# button-led-matrix-4x4.net
KiCad netlist of a schematic drawn in EAGLE
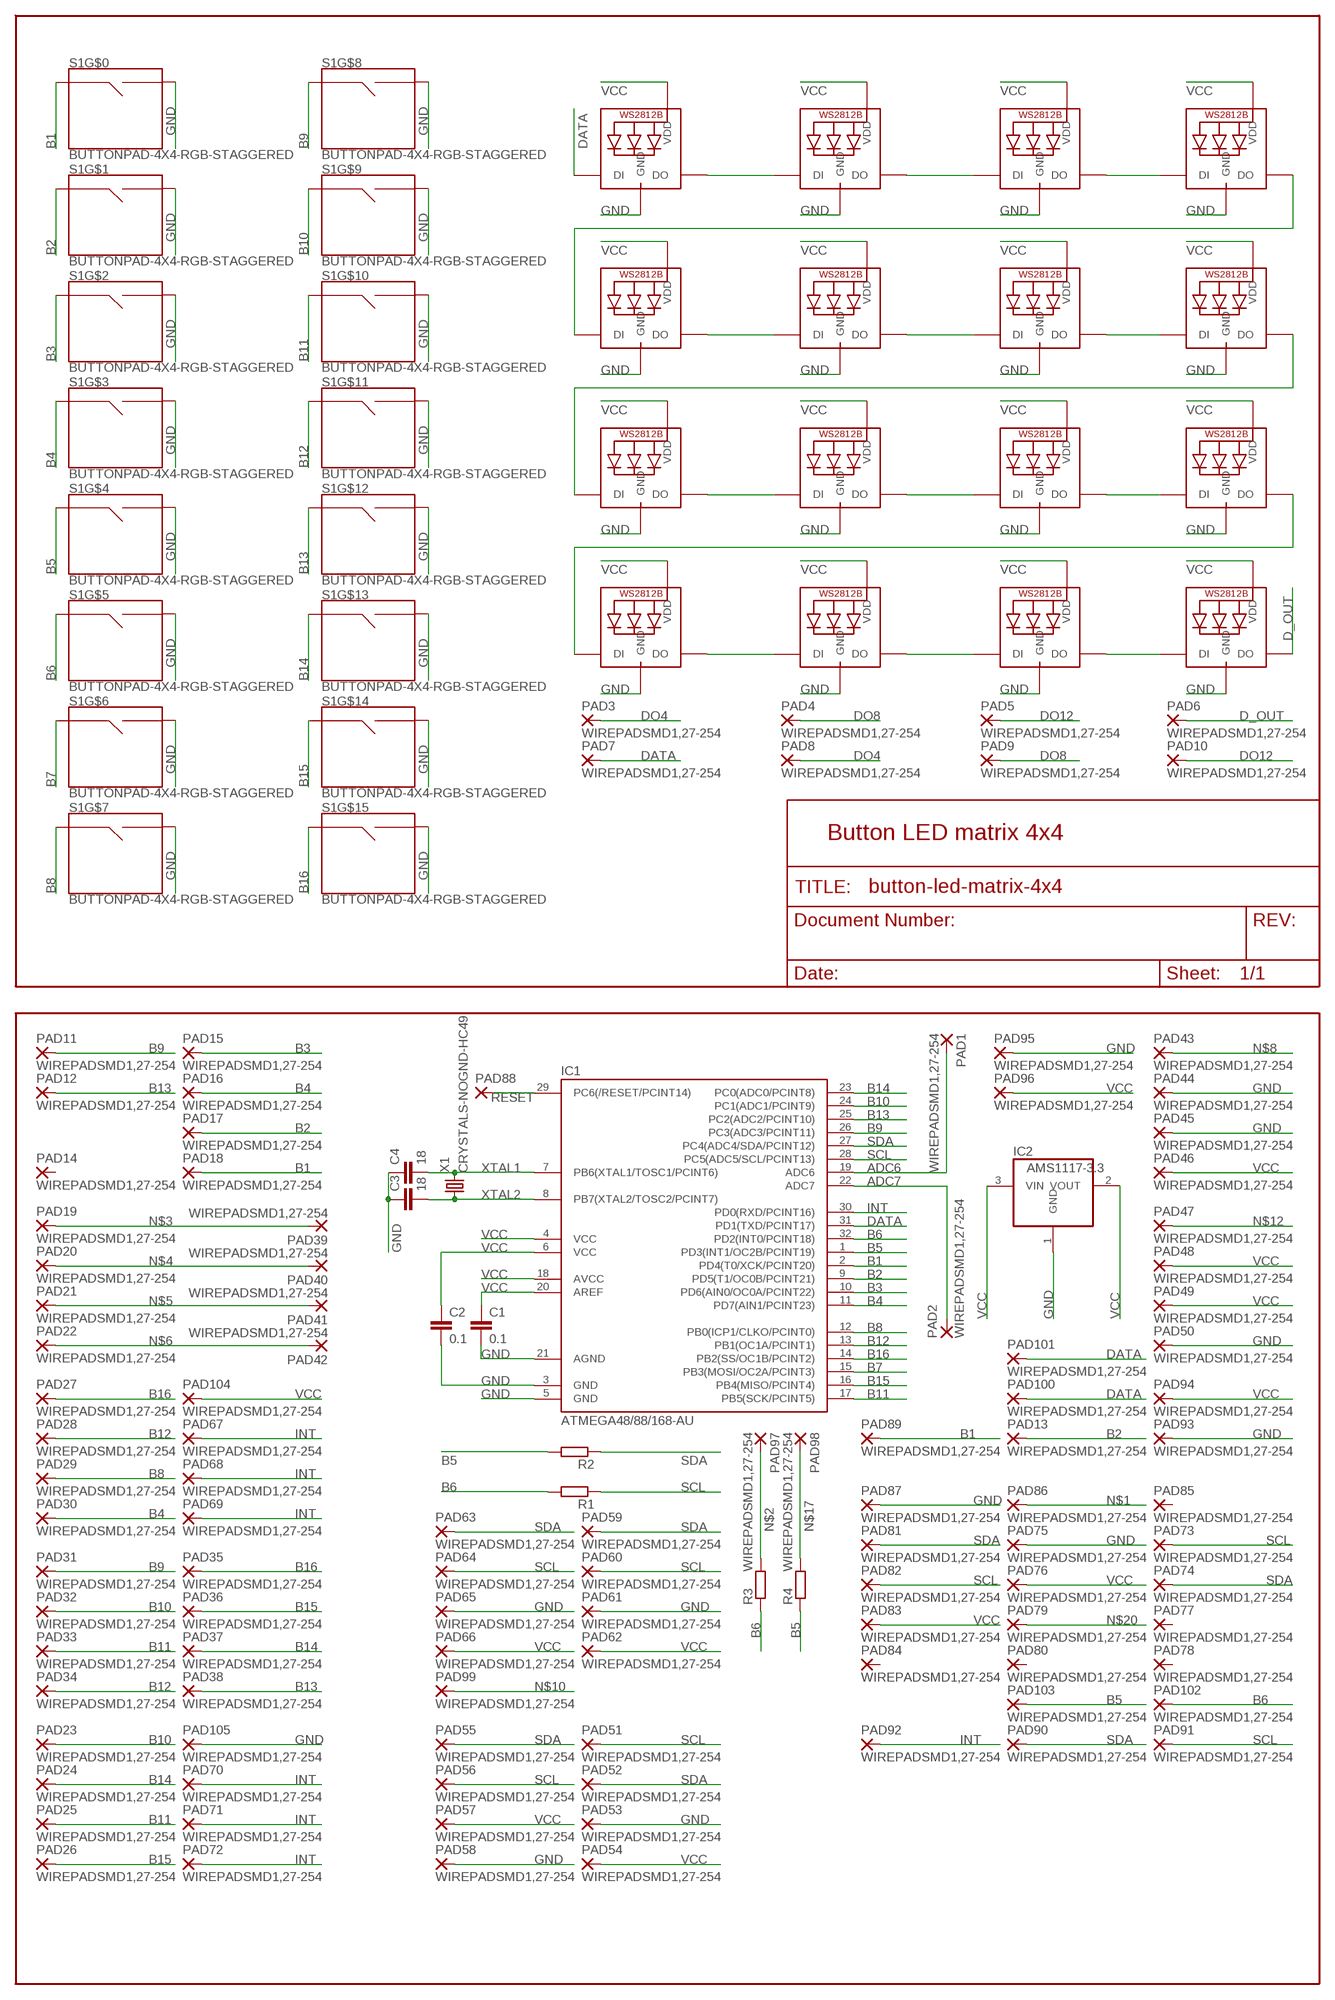
[diagram p0: schematic, sheet 1]

(export (version "E")
  (design (tool "Eeschema 10.0.6"))
  (components
    (comp (ref "C1")
      (value "0.1")
      (footprint "eagle-import:C0805")
      (libsource (lib "eagle-import") (part "C-EUC0805"))
    )
    (comp (ref "C2")
      (value "0.1")
      (footprint "eagle-import:C0805")
      (libsource (lib "eagle-import") (part "C-EUC0805"))
    )
    (comp (ref "C3")
      (value "18")
      (footprint "eagle-import:C0805")
      (libsource (lib "eagle-import") (part "C-EUC0805"))
    )
    (comp (ref "C4")
      (value "18")
      (footprint "eagle-import:C0805")
      (libsource (lib "eagle-import") (part "C-EUC0805"))
    )
    (comp (ref "IC1")
      (value "ATMEGA48/88/168-AU")
      (footprint "eagle-import:TQFP32-08")
      (libsource (lib "eagle-import") (part "ATMEGA48/88/168-AU"))
    )
    (comp (ref "IC2")
      (value "AMS1117-3.3")
      (footprint "eagle-import:SOT223")
      (fields (field (name "MPN") "REG1117"))
      (libsource (lib "eagle-import") (part "REG1117"))
    )
    (comp (ref "LED1")
      (value "WS2812B_5050N")
      (footprint "eagle-import:WS2812B-NARROW")
      (libsource (lib "eagle-import") (part "WS2812B_5050N"))
    )
    (comp (ref "LED2")
      (value "WS2812B_5050N")
      (footprint "eagle-import:WS2812B-NARROW")
      (libsource (lib "eagle-import") (part "WS2812B_5050N"))
    )
    (comp (ref "LED3")
      (value "WS2812B_5050N")
      (footprint "eagle-import:WS2812B-NARROW")
      (libsource (lib "eagle-import") (part "WS2812B_5050N"))
    )
    (comp (ref "LED4")
      (value "WS2812B_5050N")
      (footprint "eagle-import:WS2812B-NARROW")
      (libsource (lib "eagle-import") (part "WS2812B_5050N"))
    )
    (comp (ref "LED5")
      (value "WS2812B_5050N")
      (footprint "eagle-import:WS2812B-NARROW")
      (libsource (lib "eagle-import") (part "WS2812B_5050N"))
    )
    (comp (ref "LED6")
      (value "WS2812B_5050N")
      (footprint "eagle-import:WS2812B-NARROW")
      (libsource (lib "eagle-import") (part "WS2812B_5050N"))
    )
    (comp (ref "LED7")
      (value "WS2812B_5050N")
      (footprint "eagle-import:WS2812B-NARROW")
      (libsource (lib "eagle-import") (part "WS2812B_5050N"))
    )
    (comp (ref "LED8")
      (value "WS2812B_5050N")
      (footprint "eagle-import:WS2812B-NARROW")
      (libsource (lib "eagle-import") (part "WS2812B_5050N"))
    )
    (comp (ref "LED9")
      (value "WS2812B_5050N")
      (footprint "eagle-import:WS2812B-NARROW")
      (libsource (lib "eagle-import") (part "WS2812B_5050N"))
    )
    (comp (ref "LED10")
      (value "WS2812B_5050N")
      (footprint "eagle-import:WS2812B-NARROW")
      (libsource (lib "eagle-import") (part "WS2812B_5050N"))
    )
    (comp (ref "LED11")
      (value "WS2812B_5050N")
      (footprint "eagle-import:WS2812B-NARROW")
      (libsource (lib "eagle-import") (part "WS2812B_5050N"))
    )
    (comp (ref "LED12")
      (value "WS2812B_5050N")
      (footprint "eagle-import:WS2812B-NARROW")
      (libsource (lib "eagle-import") (part "WS2812B_5050N"))
    )
    (comp (ref "LED13")
      (value "WS2812B_5050N")
      (footprint "eagle-import:WS2812B-NARROW")
      (libsource (lib "eagle-import") (part "WS2812B_5050N"))
    )
    (comp (ref "LED14")
      (value "WS2812B_5050N")
      (footprint "eagle-import:WS2812B-NARROW")
      (libsource (lib "eagle-import") (part "WS2812B_5050N"))
    )
    (comp (ref "LED15")
      (value "WS2812B_5050N")
      (footprint "eagle-import:WS2812B-NARROW")
      (libsource (lib "eagle-import") (part "WS2812B_5050N"))
    )
    (comp (ref "LED16")
      (value "WS2812B_5050N")
      (footprint "eagle-import:WS2812B-NARROW")
      (libsource (lib "eagle-import") (part "WS2812B_5050N"))
    )
    (comp (ref "PAD1")
      (value "WIREPADSMD1,27-254")
      (footprint "eagle-import:SMD1,27-2,54")
      (libsource (lib "eagle-import") (part "WIREPADSMD1,27-254"))
    )
    (comp (ref "PAD2")
      (value "WIREPADSMD1,27-254")
      (footprint "eagle-import:SMD1,27-2,54")
      (libsource (lib "eagle-import") (part "WIREPADSMD1,27-254"))
    )
    (comp (ref "PAD3")
      (value "WIREPADSMD1,27-254")
      (footprint "eagle-import:SMD1,27-2,54")
      (libsource (lib "eagle-import") (part "WIREPADSMD1,27-254"))
    )
    (comp (ref "PAD4")
      (value "WIREPADSMD1,27-254")
      (footprint "eagle-import:SMD1,27-2,54")
      (libsource (lib "eagle-import") (part "WIREPADSMD1,27-254"))
    )
    (comp (ref "PAD5")
      (value "WIREPADSMD1,27-254")
      (footprint "eagle-import:SMD1,27-2,54")
      (libsource (lib "eagle-import") (part "WIREPADSMD1,27-254"))
    )
    (comp (ref "PAD6")
      (value "WIREPADSMD1,27-254")
      (footprint "eagle-import:SMD1,27-2,54")
      (libsource (lib "eagle-import") (part "WIREPADSMD1,27-254"))
    )
    (comp (ref "PAD7")
      (value "WIREPADSMD1,27-254")
      (footprint "eagle-import:SMD1,27-2,54")
      (libsource (lib "eagle-import") (part "WIREPADSMD1,27-254"))
    )
    (comp (ref "PAD8")
      (value "WIREPADSMD1,27-254")
      (footprint "eagle-import:SMD1,27-2,54")
      (libsource (lib "eagle-import") (part "WIREPADSMD1,27-254"))
    )
    (comp (ref "PAD9")
      (value "WIREPADSMD1,27-254")
      (footprint "eagle-import:SMD1,27-2,54")
      (libsource (lib "eagle-import") (part "WIREPADSMD1,27-254"))
    )
    (comp (ref "PAD10")
      (value "WIREPADSMD1,27-254")
      (footprint "eagle-import:SMD1,27-2,54")
      (libsource (lib "eagle-import") (part "WIREPADSMD1,27-254"))
    )
    (comp (ref "PAD11")
      (value "WIREPADSMD1,27-254")
      (footprint "eagle-import:SMD1,27-2,54")
      (libsource (lib "eagle-import") (part "WIREPADSMD1,27-254"))
    )
    (comp (ref "PAD12")
      (value "WIREPADSMD1,27-254")
      (footprint "eagle-import:SMD1,27-2,54")
      (libsource (lib "eagle-import") (part "WIREPADSMD1,27-254"))
    )
    (comp (ref "PAD13")
      (value "WIREPADSMD1,27-254")
      (footprint "eagle-import:SMD1,27-2,54")
      (libsource (lib "eagle-import") (part "WIREPADSMD1,27-254"))
    )
    (comp (ref "PAD14")
      (value "WIREPADSMD1,27-254")
      (footprint "eagle-import:SMD1,27-2,54")
      (libsource (lib "eagle-import") (part "WIREPADSMD1,27-254"))
    )
    (comp (ref "PAD15")
      (value "WIREPADSMD1,27-254")
      (footprint "eagle-import:SMD1,27-2,54")
      (libsource (lib "eagle-import") (part "WIREPADSMD1,27-254"))
    )
    (comp (ref "PAD16")
      (value "WIREPADSMD1,27-254")
      (footprint "eagle-import:SMD1,27-2,54")
      (libsource (lib "eagle-import") (part "WIREPADSMD1,27-254"))
    )
    (comp (ref "PAD17")
      (value "WIREPADSMD1,27-254")
      (footprint "eagle-import:SMD1,27-2,54")
      (libsource (lib "eagle-import") (part "WIREPADSMD1,27-254"))
    )
    (comp (ref "PAD18")
      (value "WIREPADSMD1,27-254")
      (footprint "eagle-import:SMD1,27-2,54")
      (libsource (lib "eagle-import") (part "WIREPADSMD1,27-254"))
    )
    (comp (ref "PAD19")
      (value "WIREPADSMD1,27-254")
      (footprint "eagle-import:SMD1,27-2,54")
      (libsource (lib "eagle-import") (part "WIREPADSMD1,27-254"))
    )
    (comp (ref "PAD20")
      (value "WIREPADSMD1,27-254")
      (footprint "eagle-import:SMD1,27-2,54")
      (libsource (lib "eagle-import") (part "WIREPADSMD1,27-254"))
    )
    (comp (ref "PAD21")
      (value "WIREPADSMD1,27-254")
      (footprint "eagle-import:SMD1,27-2,54")
      (libsource (lib "eagle-import") (part "WIREPADSMD1,27-254"))
    )
    (comp (ref "PAD22")
      (value "WIREPADSMD1,27-254")
      (footprint "eagle-import:SMD1,27-2,54")
      (libsource (lib "eagle-import") (part "WIREPADSMD1,27-254"))
    )
    (comp (ref "PAD23")
      (value "WIREPADSMD1,27-254")
      (footprint "eagle-import:SMD1,27-2,54")
      (libsource (lib "eagle-import") (part "WIREPADSMD1,27-254"))
    )
    (comp (ref "PAD24")
      (value "WIREPADSMD1,27-254")
      (footprint "eagle-import:SMD1,27-2,54")
      (libsource (lib "eagle-import") (part "WIREPADSMD1,27-254"))
    )
    (comp (ref "PAD25")
      (value "WIREPADSMD1,27-254")
      (footprint "eagle-import:SMD1,27-2,54")
      (libsource (lib "eagle-import") (part "WIREPADSMD1,27-254"))
    )
    (comp (ref "PAD26")
      (value "WIREPADSMD1,27-254")
      (footprint "eagle-import:SMD1,27-2,54")
      (libsource (lib "eagle-import") (part "WIREPADSMD1,27-254"))
    )
    (comp (ref "PAD27")
      (value "WIREPADSMD1,27-254")
      (footprint "eagle-import:SMD1,27-2,54")
      (libsource (lib "eagle-import") (part "WIREPADSMD1,27-254"))
    )
    (comp (ref "PAD28")
      (value "WIREPADSMD1,27-254")
      (footprint "eagle-import:SMD1,27-2,54")
      (libsource (lib "eagle-import") (part "WIREPADSMD1,27-254"))
    )
    (comp (ref "PAD29")
      (value "WIREPADSMD1,27-254")
      (footprint "eagle-import:SMD1,27-2,54")
      (libsource (lib "eagle-import") (part "WIREPADSMD1,27-254"))
    )
    (comp (ref "PAD30")
      (value "WIREPADSMD1,27-254")
      (footprint "eagle-import:SMD1,27-2,54")
      (libsource (lib "eagle-import") (part "WIREPADSMD1,27-254"))
    )
    (comp (ref "PAD31")
      (value "WIREPADSMD1,27-254")
      (footprint "eagle-import:SMD1,27-2,54")
      (libsource (lib "eagle-import") (part "WIREPADSMD1,27-254"))
    )
    (comp (ref "PAD32")
      (value "WIREPADSMD1,27-254")
      (footprint "eagle-import:SMD1,27-2,54")
      (libsource (lib "eagle-import") (part "WIREPADSMD1,27-254"))
    )
    (comp (ref "PAD33")
      (value "WIREPADSMD1,27-254")
      (footprint "eagle-import:SMD1,27-2,54")
      (libsource (lib "eagle-import") (part "WIREPADSMD1,27-254"))
    )
    (comp (ref "PAD34")
      (value "WIREPADSMD1,27-254")
      (footprint "eagle-import:SMD1,27-2,54")
      (libsource (lib "eagle-import") (part "WIREPADSMD1,27-254"))
    )
    (comp (ref "PAD35")
      (value "WIREPADSMD1,27-254")
      (footprint "eagle-import:SMD1,27-2,54")
      (libsource (lib "eagle-import") (part "WIREPADSMD1,27-254"))
    )
    (comp (ref "PAD36")
      (value "WIREPADSMD1,27-254")
      (footprint "eagle-import:SMD1,27-2,54")
      (libsource (lib "eagle-import") (part "WIREPADSMD1,27-254"))
    )
    (comp (ref "PAD37")
      (value "WIREPADSMD1,27-254")
      (footprint "eagle-import:SMD1,27-2,54")
      (libsource (lib "eagle-import") (part "WIREPADSMD1,27-254"))
    )
    (comp (ref "PAD38")
      (value "WIREPADSMD1,27-254")
      (footprint "eagle-import:SMD1,27-2,54")
      (libsource (lib "eagle-import") (part "WIREPADSMD1,27-254"))
    )
    (comp (ref "PAD39")
      (value "WIREPADSMD1,27-254")
      (footprint "eagle-import:SMD1,27-2,54")
      (libsource (lib "eagle-import") (part "WIREPADSMD1,27-254"))
    )
    (comp (ref "PAD40")
      (value "WIREPADSMD1,27-254")
      (footprint "eagle-import:SMD1,27-2,54")
      (libsource (lib "eagle-import") (part "WIREPADSMD1,27-254"))
    )
    (comp (ref "PAD41")
      (value "WIREPADSMD1,27-254")
      (footprint "eagle-import:SMD1,27-2,54")
      (libsource (lib "eagle-import") (part "WIREPADSMD1,27-254"))
    )
    (comp (ref "PAD42")
      (value "WIREPADSMD1,27-254")
      (footprint "eagle-import:SMD1,27-2,54")
      (libsource (lib "eagle-import") (part "WIREPADSMD1,27-254"))
    )
    (comp (ref "PAD43")
      (value "WIREPADSMD1,27-254")
      (footprint "eagle-import:SMD1,27-2,54")
      (libsource (lib "eagle-import") (part "WIREPADSMD1,27-254"))
    )
    (comp (ref "PAD44")
      (value "WIREPADSMD1,27-254")
      (footprint "eagle-import:SMD1,27-2,54")
      (libsource (lib "eagle-import") (part "WIREPADSMD1,27-254"))
    )
    (comp (ref "PAD45")
      (value "WIREPADSMD1,27-254")
      (footprint "eagle-import:SMD1,27-2,54")
      (libsource (lib "eagle-import") (part "WIREPADSMD1,27-254"))
    )
    (comp (ref "PAD46")
      (value "WIREPADSMD1,27-254")
      (footprint "eagle-import:SMD1,27-2,54")
      (libsource (lib "eagle-import") (part "WIREPADSMD1,27-254"))
    )
    (comp (ref "PAD47")
      (value "WIREPADSMD1,27-254")
      (footprint "eagle-import:SMD1,27-2,54")
      (libsource (lib "eagle-import") (part "WIREPADSMD1,27-254"))
    )
    (comp (ref "PAD48")
      (value "WIREPADSMD1,27-254")
      (footprint "eagle-import:SMD1,27-2,54")
      (libsource (lib "eagle-import") (part "WIREPADSMD1,27-254"))
    )
    (comp (ref "PAD49")
      (value "WIREPADSMD1,27-254")
      (footprint "eagle-import:SMD1,27-2,54")
      (libsource (lib "eagle-import") (part "WIREPADSMD1,27-254"))
    )
    (comp (ref "PAD50")
      (value "WIREPADSMD1,27-254")
      (footprint "eagle-import:SMD1,27-2,54")
      (libsource (lib "eagle-import") (part "WIREPADSMD1,27-254"))
    )
    (comp (ref "PAD51")
      (value "WIREPADSMD1,27-254")
      (footprint "eagle-import:SMD1,27-2,54")
      (libsource (lib "eagle-import") (part "WIREPADSMD1,27-254"))
    )
    (comp (ref "PAD52")
      (value "WIREPADSMD1,27-254")
      (footprint "eagle-import:SMD1,27-2,54")
      (libsource (lib "eagle-import") (part "WIREPADSMD1,27-254"))
    )
    (comp (ref "PAD53")
      (value "WIREPADSMD1,27-254")
      (footprint "eagle-import:SMD1,27-2,54")
      (libsource (lib "eagle-import") (part "WIREPADSMD1,27-254"))
    )
    (comp (ref "PAD54")
      (value "WIREPADSMD1,27-254")
      (footprint "eagle-import:SMD1,27-2,54")
      (libsource (lib "eagle-import") (part "WIREPADSMD1,27-254"))
    )
    (comp (ref "PAD55")
      (value "WIREPADSMD1,27-254")
      (footprint "eagle-import:SMD1,27-2,54")
      (libsource (lib "eagle-import") (part "WIREPADSMD1,27-254"))
    )
    (comp (ref "PAD56")
      (value "WIREPADSMD1,27-254")
      (footprint "eagle-import:SMD1,27-2,54")
      (libsource (lib "eagle-import") (part "WIREPADSMD1,27-254"))
    )
    (comp (ref "PAD57")
      (value "WIREPADSMD1,27-254")
      (footprint "eagle-import:SMD1,27-2,54")
      (libsource (lib "eagle-import") (part "WIREPADSMD1,27-254"))
    )
    (comp (ref "PAD58")
      (value "WIREPADSMD1,27-254")
      (footprint "eagle-import:SMD1,27-2,54")
      (libsource (lib "eagle-import") (part "WIREPADSMD1,27-254"))
    )
    (comp (ref "PAD59")
      (value "WIREPADSMD1,27-254")
      (footprint "eagle-import:SMD1,27-2,54")
      (libsource (lib "eagle-import") (part "WIREPADSMD1,27-254"))
    )
    (comp (ref "PAD60")
      (value "WIREPADSMD1,27-254")
      (footprint "eagle-import:SMD1,27-2,54")
      (libsource (lib "eagle-import") (part "WIREPADSMD1,27-254"))
    )
    (comp (ref "PAD61")
      (value "WIREPADSMD1,27-254")
      (footprint "eagle-import:SMD1,27-2,54")
      (libsource (lib "eagle-import") (part "WIREPADSMD1,27-254"))
    )
    (comp (ref "PAD62")
      (value "WIREPADSMD1,27-254")
      (footprint "eagle-import:SMD1,27-2,54")
      (libsource (lib "eagle-import") (part "WIREPADSMD1,27-254"))
    )
    (comp (ref "PAD63")
      (value "WIREPADSMD1,27-254")
      (footprint "eagle-import:SMD1,27-2,54")
      (libsource (lib "eagle-import") (part "WIREPADSMD1,27-254"))
    )
    (comp (ref "PAD64")
      (value "WIREPADSMD1,27-254")
      (footprint "eagle-import:SMD1,27-2,54")
      (libsource (lib "eagle-import") (part "WIREPADSMD1,27-254"))
    )
    (comp (ref "PAD65")
      (value "WIREPADSMD1,27-254")
      (footprint "eagle-import:SMD1,27-2,54")
      (libsource (lib "eagle-import") (part "WIREPADSMD1,27-254"))
    )
    (comp (ref "PAD66")
      (value "WIREPADSMD1,27-254")
      (footprint "eagle-import:SMD1,27-2,54")
      (libsource (lib "eagle-import") (part "WIREPADSMD1,27-254"))
    )
    (comp (ref "PAD67")
      (value "WIREPADSMD1,27-254")
      (footprint "eagle-import:SMD1,27-2,54")
      (libsource (lib "eagle-import") (part "WIREPADSMD1,27-254"))
    )
    (comp (ref "PAD68")
      (value "WIREPADSMD1,27-254")
      (footprint "eagle-import:SMD1,27-2,54")
      (libsource (lib "eagle-import") (part "WIREPADSMD1,27-254"))
    )
    (comp (ref "PAD69")
      (value "WIREPADSMD1,27-254")
      (footprint "eagle-import:SMD1,27-2,54")
      (libsource (lib "eagle-import") (part "WIREPADSMD1,27-254"))
    )
    (comp (ref "PAD70")
      (value "WIREPADSMD1,27-254")
      (footprint "eagle-import:SMD1,27-2,54")
      (libsource (lib "eagle-import") (part "WIREPADSMD1,27-254"))
    )
    (comp (ref "PAD71")
      (value "WIREPADSMD1,27-254")
      (footprint "eagle-import:SMD1,27-2,54")
      (libsource (lib "eagle-import") (part "WIREPADSMD1,27-254"))
    )
    (comp (ref "PAD72")
      (value "WIREPADSMD1,27-254")
      (footprint "eagle-import:SMD1,27-2,54")
      (libsource (lib "eagle-import") (part "WIREPADSMD1,27-254"))
    )
    (comp (ref "PAD73")
      (value "WIREPADSMD1,27-254")
      (footprint "eagle-import:SMD1,27-2,54")
      (libsource (lib "eagle-import") (part "WIREPADSMD1,27-254"))
    )
    (comp (ref "PAD74")
      (value "WIREPADSMD1,27-254")
      (footprint "eagle-import:SMD1,27-2,54")
      (libsource (lib "eagle-import") (part "WIREPADSMD1,27-254"))
    )
    (comp (ref "PAD75")
      (value "WIREPADSMD1,27-254")
      (footprint "eagle-import:SMD1,27-2,54")
      (libsource (lib "eagle-import") (part "WIREPADSMD1,27-254"))
    )
    (comp (ref "PAD76")
      (value "WIREPADSMD1,27-254")
      (footprint "eagle-import:SMD1,27-2,54")
      (libsource (lib "eagle-import") (part "WIREPADSMD1,27-254"))
    )
    (comp (ref "PAD77")
      (value "WIREPADSMD1,27-254")
      (footprint "eagle-import:SMD1,27-2,54")
      (libsource (lib "eagle-import") (part "WIREPADSMD1,27-254"))
    )
    (comp (ref "PAD78")
      (value "WIREPADSMD1,27-254")
      (footprint "eagle-import:SMD1,27-2,54")
      (libsource (lib "eagle-import") (part "WIREPADSMD1,27-254"))
    )
    (comp (ref "PAD79")
      (value "WIREPADSMD1,27-254")
      (footprint "eagle-import:SMD1,27-2,54")
      (libsource (lib "eagle-import") (part "WIREPADSMD1,27-254"))
    )
    (comp (ref "PAD80")
      (value "WIREPADSMD1,27-254")
      (footprint "eagle-import:SMD1,27-2,54")
      (libsource (lib "eagle-import") (part "WIREPADSMD1,27-254"))
    )
    (comp (ref "PAD81")
      (value "WIREPADSMD1,27-254")
      (footprint "eagle-import:SMD1,27-2,54")
      (libsource (lib "eagle-import") (part "WIREPADSMD1,27-254"))
    )
    (comp (ref "PAD82")
      (value "WIREPADSMD1,27-254")
      (footprint "eagle-import:SMD1,27-2,54")
      (libsource (lib "eagle-import") (part "WIREPADSMD1,27-254"))
    )
    (comp (ref "PAD83")
      (value "WIREPADSMD1,27-254")
      (footprint "eagle-import:SMD1,27-2,54")
      (libsource (lib "eagle-import") (part "WIREPADSMD1,27-254"))
    )
    (comp (ref "PAD84")
      (value "WIREPADSMD1,27-254")
      (footprint "eagle-import:SMD1,27-2,54")
      (libsource (lib "eagle-import") (part "WIREPADSMD1,27-254"))
    )
    (comp (ref "PAD85")
      (value "WIREPADSMD1,27-254")
      (footprint "eagle-import:SMD1,27-2,54")
      (libsource (lib "eagle-import") (part "WIREPADSMD1,27-254"))
    )
    (comp (ref "PAD86")
      (value "WIREPADSMD1,27-254")
      (footprint "eagle-import:SMD1,27-2,54")
      (libsource (lib "eagle-import") (part "WIREPADSMD1,27-254"))
    )
    (comp (ref "PAD87")
      (value "WIREPADSMD1,27-254")
      (footprint "eagle-import:SMD1,27-2,54")
      (libsource (lib "eagle-import") (part "WIREPADSMD1,27-254"))
    )
    (comp (ref "PAD88")
      (value "1,6/0,8")
      (footprint "eagle-import:1,6_0,8")
      (libsource (lib "eagle-import") (part "1,6/0,8"))
    )
    (comp (ref "PAD89")
      (value "WIREPADSMD1,27-254")
      (footprint "eagle-import:SMD1,27-2,54")
      (libsource (lib "eagle-import") (part "WIREPADSMD1,27-254"))
    )
    (comp (ref "PAD90")
      (value "WIREPADSMD1,27-254")
      (footprint "eagle-import:SMD1,27-2,54")
      (libsource (lib "eagle-import") (part "WIREPADSMD1,27-254"))
    )
    (comp (ref "PAD91")
      (value "WIREPADSMD1,27-254")
      (footprint "eagle-import:SMD1,27-2,54")
      (libsource (lib "eagle-import") (part "WIREPADSMD1,27-254"))
    )
    (comp (ref "PAD92")
      (value "WIREPADSMD1,27-254")
      (footprint "eagle-import:SMD1,27-2,54")
      (libsource (lib "eagle-import") (part "WIREPADSMD1,27-254"))
    )
    (comp (ref "PAD93")
      (value "WIREPADSMD1,27-254")
      (footprint "eagle-import:SMD1,27-2,54")
      (libsource (lib "eagle-import") (part "WIREPADSMD1,27-254"))
    )
    (comp (ref "PAD94")
      (value "WIREPADSMD1,27-254")
      (footprint "eagle-import:SMD1,27-2,54")
      (libsource (lib "eagle-import") (part "WIREPADSMD1,27-254"))
    )
    (comp (ref "PAD95")
      (value "WIREPADSMD1,27-254")
      (footprint "eagle-import:SMD1,27-2,54")
      (libsource (lib "eagle-import") (part "WIREPADSMD1,27-254"))
    )
    (comp (ref "PAD96")
      (value "WIREPADSMD1,27-254")
      (footprint "eagle-import:SMD1,27-2,54")
      (libsource (lib "eagle-import") (part "WIREPADSMD1,27-254"))
    )
    (comp (ref "PAD97")
      (value "WIREPADSMD1,27-254")
      (footprint "eagle-import:SMD1,27-2,54")
      (libsource (lib "eagle-import") (part "WIREPADSMD1,27-254"))
    )
    (comp (ref "PAD98")
      (value "WIREPADSMD1,27-254")
      (footprint "eagle-import:SMD1,27-2,54")
      (libsource (lib "eagle-import") (part "WIREPADSMD1,27-254"))
    )
    (comp (ref "PAD99")
      (value "WIREPADSMD1,27-254")
      (footprint "eagle-import:SMD1,27-2,54")
      (libsource (lib "eagle-import") (part "WIREPADSMD1,27-254"))
    )
    (comp (ref "PAD100")
      (value "WIREPADSMD1,27-254")
      (footprint "eagle-import:SMD1,27-2,54")
      (libsource (lib "eagle-import") (part "WIREPADSMD1,27-254"))
    )
    (comp (ref "PAD101")
      (value "WIREPADSMD1,27-254")
      (footprint "eagle-import:SMD1,27-2,54")
      (libsource (lib "eagle-import") (part "WIREPADSMD1,27-254"))
    )
    (comp (ref "PAD102")
      (value "WIREPADSMD1,27-254")
      (footprint "eagle-import:SMD1,27-2,54")
      (libsource (lib "eagle-import") (part "WIREPADSMD1,27-254"))
    )
    (comp (ref "PAD103")
      (value "WIREPADSMD1,27-254")
      (footprint "eagle-import:SMD1,27-2,54")
      (libsource (lib "eagle-import") (part "WIREPADSMD1,27-254"))
    )
    (comp (ref "PAD104")
      (value "WIREPADSMD1,27-254")
      (footprint "eagle-import:SMD1,27-2,54")
      (libsource (lib "eagle-import") (part "WIREPADSMD1,27-254"))
    )
    (comp (ref "PAD105")
      (value "WIREPADSMD1,27-254")
      (footprint "eagle-import:SMD1,27-2,54")
      (libsource (lib "eagle-import") (part "WIREPADSMD1,27-254"))
    )
    (comp (ref "R1")
      (value "R-EU_R1206")
      (footprint "eagle-import:R1206")
      (libsource (lib "eagle-import") (part "R-EU_R1206"))
    )
    (comp (ref "R2")
      (value "R-EU_R1206")
      (footprint "eagle-import:R1206")
      (libsource (lib "eagle-import") (part "R-EU_R1206"))
    )
    (comp (ref "R3")
      (value "R-EU_R0805")
      (footprint "eagle-import:R0805")
      (libsource (lib "eagle-import") (part "R-EU_R0805"))
    )
    (comp (ref "R4")
      (value "R-EU_R0805")
      (footprint "eagle-import:R0805")
      (libsource (lib "eagle-import") (part "R-EU_R0805"))
    )
    (comp (ref "S1")
      (value "BUTTONPAD-4X4-RGB-STAGGERED")
      (footprint "eagle-import:BUTTONPAD-4X4-STAGGERED")
      (libsource (lib "eagle-import") (part "BUTTONPAD-4X4-RGB-STAGGERED"))
    )
    (comp (ref "X1")
      (value "CRYSTALS-NOGND-HC49")
      (footprint "eagle-import:HC49")
      (libsource (lib "eagle-import") (part "CRYSTALS-NOGND-HC49"))
    )
  )
  (nets
    (net (code "1") (name "/ADC6") (class "Default")
      (node (ref "IC1") (pin "19") (pinfunction "ADC6_19") (pintype "passive"))
      (node (ref "PAD1") (pin "1") (pinfunction "P_1") (pintype "passive"))
    )
    (net (code "2") (name "/ADC7") (class "Default")
      (node (ref "IC1") (pin "22") (pinfunction "ADC7_22") (pintype "passive"))
      (node (ref "PAD2") (pin "1") (pinfunction "P_1") (pintype "passive"))
    )
    (net (code "3") (name "/B1") (class "Default")
      (node (ref "IC1") (pin "2") (pinfunction "PD4(T0/XCK/PCINT20)_2") (pintype "bidirectional"))
      (node (ref "PAD18") (pin "1") (pinfunction "P_1") (pintype "passive"))
      (node (ref "PAD89") (pin "1") (pinfunction "P_1") (pintype "passive"))
      (node (ref "S1") (pin "SIG0") (pinfunction "SIG1_SIG0") (pintype "bidirectional"))
    )
    (net (code "4") (name "/B2") (class "Default")
      (node (ref "IC1") (pin "9") (pinfunction "PD5(T1/OC0B/PCINT21)_9") (pintype "bidirectional"))
      (node (ref "PAD13") (pin "1") (pinfunction "P_1") (pintype "passive"))
      (node (ref "PAD17") (pin "1") (pinfunction "P_1") (pintype "passive"))
      (node (ref "S1") (pin "SIG2") (pinfunction "SIG1_SIG2") (pintype "bidirectional"))
    )
    (net (code "5") (name "/B3") (class "Default")
      (node (ref "IC1") (pin "10") (pinfunction "PD6(AIN0/OC0A/PCINT22)_10") (pintype "bidirectional"))
      (node (ref "PAD15") (pin "1") (pinfunction "P_1") (pintype "passive"))
      (node (ref "S1") (pin "SIG4") (pinfunction "SIG1_SIG4") (pintype "bidirectional"))
    )
    (net (code "6") (name "/B4") (class "Default")
      (node (ref "IC1") (pin "11") (pinfunction "PD7(AIN1/PCINT23)_11") (pintype "bidirectional"))
      (node (ref "PAD16") (pin "1") (pinfunction "P_1") (pintype "passive"))
      (node (ref "PAD30") (pin "1") (pinfunction "P_1") (pintype "passive"))
      (node (ref "S1") (pin "SIG6") (pinfunction "SIG1_SIG6") (pintype "bidirectional"))
    )
    (net (code "7") (name "/B5") (class "Default")
      (node (ref "IC1") (pin "1") (pinfunction "PD3(INT1/OC2B/PCINT19)_1") (pintype "bidirectional"))
      (node (ref "PAD103") (pin "1") (pinfunction "P_1") (pintype "passive"))
      (node (ref "R2") (pin "2") (pinfunction "2_2") (pintype "passive"))
      (node (ref "R4") (pin "1") (pinfunction "1_1") (pintype "passive"))
      (node (ref "S1") (pin "SIG8") (pinfunction "SIG1_SIG8") (pintype "bidirectional"))
    )
    (net (code "8") (name "/B6") (class "Default")
      (node (ref "IC1") (pin "32") (pinfunction "PD2(INT0/PCINT18)_32") (pintype "bidirectional"))
      (node (ref "PAD102") (pin "1") (pinfunction "P_1") (pintype "passive"))
      (node (ref "R1") (pin "2") (pinfunction "2_2") (pintype "passive"))
      (node (ref "R3") (pin "1") (pinfunction "1_1") (pintype "passive"))
      (node (ref "S1") (pin "SIG10") (pinfunction "SIG1_SIG10") (pintype "bidirectional"))
    )
    (net (code "9") (name "/B7") (class "Default")
      (node (ref "IC1") (pin "15") (pinfunction "PB3(MOSI/OC2A/PCINT3)_15") (pintype "bidirectional"))
      (node (ref "S1") (pin "SIG12") (pinfunction "SIG1_SIG12") (pintype "bidirectional"))
    )
    (net (code "10") (name "/B8") (class "Default")
      (node (ref "IC1") (pin "12") (pinfunction "PB0(ICP1/CLKO/PCINT0)_12") (pintype "bidirectional"))
      (node (ref "PAD29") (pin "1") (pinfunction "P_1") (pintype "passive"))
      (node (ref "S1") (pin "SIG14") (pinfunction "SIG1_SIG14") (pintype "bidirectional"))
    )
    (net (code "11") (name "/B9") (class "Default")
      (node (ref "IC1") (pin "26") (pinfunction "PC3(ADC3/PCINT11)_26") (pintype "bidirectional"))
      (node (ref "PAD11") (pin "1") (pinfunction "P_1") (pintype "passive"))
      (node (ref "PAD31") (pin "1") (pinfunction "P_1") (pintype "passive"))
      (node (ref "S1") (pin "SIG16") (pinfunction "SIG1_SIG16") (pintype "bidirectional"))
    )
    (net (code "12") (name "/B10") (class "Default")
      (node (ref "IC1") (pin "24") (pinfunction "PC1(ADC1/PCINT9)_24") (pintype "bidirectional"))
      (node (ref "PAD23") (pin "1") (pinfunction "P_1") (pintype "passive"))
      (node (ref "PAD32") (pin "1") (pinfunction "P_1") (pintype "passive"))
      (node (ref "S1") (pin "SIG18") (pinfunction "SIG1_SIG18") (pintype "bidirectional"))
    )
    (net (code "13") (name "/B11") (class "Default")
      (node (ref "IC1") (pin "17") (pinfunction "PB5(SCK/PCINT5)_17") (pintype "bidirectional"))
      (node (ref "PAD25") (pin "1") (pinfunction "P_1") (pintype "passive"))
      (node (ref "PAD33") (pin "1") (pinfunction "P_1") (pintype "passive"))
      (node (ref "S1") (pin "SIG20") (pinfunction "SIG1_SIG20") (pintype "bidirectional"))
    )
    (net (code "14") (name "/B12") (class "Default")
      (node (ref "IC1") (pin "13") (pinfunction "PB1(OC1A/PCINT1)_13") (pintype "bidirectional"))
      (node (ref "PAD28") (pin "1") (pinfunction "P_1") (pintype "passive"))
      (node (ref "PAD34") (pin "1") (pinfunction "P_1") (pintype "passive"))
      (node (ref "S1") (pin "SIG22") (pinfunction "SIG1_SIG22") (pintype "bidirectional"))
    )
    (net (code "15") (name "/B13") (class "Default")
      (node (ref "IC1") (pin "25") (pinfunction "PC2(ADC2/PCINT10)_25") (pintype "bidirectional"))
      (node (ref "PAD12") (pin "1") (pinfunction "P_1") (pintype "passive"))
      (node (ref "PAD38") (pin "1") (pinfunction "P_1") (pintype "passive"))
      (node (ref "S1") (pin "SIG24") (pinfunction "SIG1_SIG24") (pintype "bidirectional"))
    )
    (net (code "16") (name "/B14") (class "Default")
      (node (ref "IC1") (pin "23") (pinfunction "PC0(ADC0/PCINT8)_23") (pintype "bidirectional"))
      (node (ref "PAD24") (pin "1") (pinfunction "P_1") (pintype "passive"))
      (node (ref "PAD37") (pin "1") (pinfunction "P_1") (pintype "passive"))
      (node (ref "S1") (pin "SIG26") (pinfunction "SIG1_SIG26") (pintype "bidirectional"))
    )
    (net (code "17") (name "/B15") (class "Default")
      (node (ref "IC1") (pin "16") (pinfunction "PB4(MISO/PCINT4)_16") (pintype "bidirectional"))
      (node (ref "PAD26") (pin "1") (pinfunction "P_1") (pintype "passive"))
      (node (ref "PAD36") (pin "1") (pinfunction "P_1") (pintype "passive"))
      (node (ref "S1") (pin "SIG28") (pinfunction "SIG1_SIG28") (pintype "bidirectional"))
    )
    (net (code "18") (name "/B16") (class "Default")
      (node (ref "IC1") (pin "14") (pinfunction "PB2(SS/OC1B/PCINT2)_14") (pintype "bidirectional"))
      (node (ref "PAD27") (pin "1") (pinfunction "P_1") (pintype "passive"))
      (node (ref "PAD35") (pin "1") (pinfunction "P_1") (pintype "passive"))
      (node (ref "S1") (pin "SIG30") (pinfunction "SIG1_SIG30") (pintype "bidirectional"))
    )
    (net (code "19") (name "/DATA") (class "Default")
      (node (ref "IC1") (pin "31") (pinfunction "PD1(TXD/PCINT17)_31") (pintype "bidirectional"))
      (node (ref "LED1") (pin "4-DIN") (pinfunction "DI_4-DIN") (pintype "input"))
      (node (ref "PAD100") (pin "1") (pinfunction "P_1") (pintype "passive"))
      (node (ref "PAD101") (pin "1") (pinfunction "P_1") (pintype "passive"))
      (node (ref "PAD7") (pin "1") (pinfunction "P_1") (pintype "passive"))
    )
    (net (code "20") (name "/DO4") (class "Default")
      (node (ref "LED4") (pin "2-DOUT") (pinfunction "DO_2-DOUT") (pintype "output"))
      (node (ref "LED5") (pin "4-DIN") (pinfunction "DI_4-DIN") (pintype "input"))
      (node (ref "PAD3") (pin "1") (pinfunction "P_1") (pintype "passive"))
      (node (ref "PAD8") (pin "1") (pinfunction "P_1") (pintype "passive"))
    )
    (net (code "21") (name "/DO8") (class "Default")
      (node (ref "LED8") (pin "2-DOUT") (pinfunction "DO_2-DOUT") (pintype "output"))
      (node (ref "LED9") (pin "4-DIN") (pinfunction "DI_4-DIN") (pintype "input"))
      (node (ref "PAD4") (pin "1") (pinfunction "P_1") (pintype "passive"))
      (node (ref "PAD9") (pin "1") (pinfunction "P_1") (pintype "passive"))
    )
    (net (code "22") (name "/DO12") (class "Default")
      (node (ref "LED12") (pin "2-DOUT") (pinfunction "DO_2-DOUT") (pintype "output"))
      (node (ref "LED13") (pin "4-DIN") (pinfunction "DI_4-DIN") (pintype "input"))
      (node (ref "PAD10") (pin "1") (pinfunction "P_1") (pintype "passive"))
      (node (ref "PAD5") (pin "1") (pinfunction "P_1") (pintype "passive"))
    )
    (net (code "23") (name "/D_OUT") (class "Default")
      (node (ref "LED16") (pin "2-DOUT") (pinfunction "DO_2-DOUT") (pintype "output"))
      (node (ref "PAD6") (pin "1") (pinfunction "P_1") (pintype "passive"))
    )
    (net (code "24") (name "/GND") (class "Default")
      (node (ref "C1") (pin "2") (pinfunction "2_2") (pintype "passive"))
      (node (ref "C2") (pin "2") (pinfunction "2_2") (pintype "passive"))
      (node (ref "C3") (pin "1") (pinfunction "1_1") (pintype "passive"))
      (node (ref "C4") (pin "1") (pinfunction "1_1") (pintype "passive"))
      (node (ref "IC1") (pin "21") (pinfunction "AGND_21") (pintype "power_in"))
      (node (ref "IC1") (pin "3") (pinfunction "GND_3") (pintype "power_in"))
      (node (ref "IC1") (pin "5") (pinfunction "GND_5") (pintype "power_in"))
      (node (ref "IC2") (pin "1") (pinfunction "GND_1") (pintype "power_in"))
      (node (ref "LED1") (pin "3-GND") (pinfunction "GND_3-GND") (pintype "power_in"))
      (node (ref "LED10") (pin "3-GND") (pinfunction "GND_3-GND") (pintype "power_in"))
      (node (ref "LED11") (pin "3-GND") (pinfunction "GND_3-GND") (pintype "power_in"))
      (node (ref "LED12") (pin "3-GND") (pinfunction "GND_3-GND") (pintype "power_in"))
      (node (ref "LED13") (pin "3-GND") (pinfunction "GND_3-GND") (pintype "power_in"))
      (node (ref "LED14") (pin "3-GND") (pinfunction "GND_3-GND") (pintype "power_in"))
      (node (ref "LED15") (pin "3-GND") (pinfunction "GND_3-GND") (pintype "power_in"))
      (node (ref "LED16") (pin "3-GND") (pinfunction "GND_3-GND") (pintype "power_in"))
      (node (ref "LED2") (pin "3-GND") (pinfunction "GND_3-GND") (pintype "power_in"))
      (node (ref "LED3") (pin "3-GND") (pinfunction "GND_3-GND") (pintype "power_in"))
      (node (ref "LED4") (pin "3-GND") (pinfunction "GND_3-GND") (pintype "power_in"))
      (node (ref "LED5") (pin "3-GND") (pinfunction "GND_3-GND") (pintype "power_in"))
      (node (ref "LED6") (pin "3-GND") (pinfunction "GND_3-GND") (pintype "power_in"))
      (node (ref "LED7") (pin "3-GND") (pinfunction "GND_3-GND") (pintype "power_in"))
      (node (ref "LED8") (pin "3-GND") (pinfunction "GND_3-GND") (pintype "power_in"))
      (node (ref "LED9") (pin "3-GND") (pinfunction "GND_3-GND") (pintype "power_in"))
      (node (ref "PAD105") (pin "1") (pinfunction "P_1") (pintype "passive"))
      (node (ref "PAD44") (pin "1") (pinfunction "P_1") (pintype "passive"))
      (node (ref "PAD45") (pin "1") (pinfunction "P_1") (pintype "passive"))
      (node (ref "PAD50") (pin "1") (pinfunction "P_1") (pintype "passive"))
      (node (ref "PAD53") (pin "1") (pinfunction "P_1") (pintype "passive"))
      (node (ref "PAD58") (pin "1") (pinfunction "P_1") (pintype "passive"))
      (node (ref "PAD61") (pin "1") (pinfunction "P_1") (pintype "passive"))
      (node (ref "PAD65") (pin "1") (pinfunction "P_1") (pintype "passive"))
      (node (ref "PAD75") (pin "1") (pinfunction "P_1") (pintype "passive"))
      (node (ref "PAD87") (pin "1") (pinfunction "P_1") (pintype "passive"))
      (node (ref "PAD93") (pin "1") (pinfunction "P_1") (pintype "passive"))
      (node (ref "PAD95") (pin "1") (pinfunction "P_1") (pintype "passive"))
      (node (ref "S1") (pin "SIG1") (pinfunction "SIG2_SIG1") (pintype "bidirectional"))
      (node (ref "S1") (pin "SIG11") (pinfunction "SIG2_SIG11") (pintype "bidirectional"))
      (node (ref "S1") (pin "SIG13") (pinfunction "SIG2_SIG13") (pintype "bidirectional"))
      (node (ref "S1") (pin "SIG15") (pinfunction "SIG2_SIG15") (pintype "bidirectional"))
      (node (ref "S1") (pin "SIG17") (pinfunction "SIG2_SIG17") (pintype "bidirectional"))
      (node (ref "S1") (pin "SIG19") (pinfunction "SIG2_SIG19") (pintype "bidirectional"))
      (node (ref "S1") (pin "SIG21") (pinfunction "SIG2_SIG21") (pintype "bidirectional"))
      (node (ref "S1") (pin "SIG23") (pinfunction "SIG2_SIG23") (pintype "bidirectional"))
      (node (ref "S1") (pin "SIG25") (pinfunction "SIG2_SIG25") (pintype "bidirectional"))
      (node (ref "S1") (pin "SIG27") (pinfunction "SIG2_SIG27") (pintype "bidirectional"))
      (node (ref "S1") (pin "SIG29") (pinfunction "SIG2_SIG29") (pintype "bidirectional"))
      (node (ref "S1") (pin "SIG3") (pinfunction "SIG2_SIG3") (pintype "bidirectional"))
      (node (ref "S1") (pin "SIG31") (pinfunction "SIG2_SIG31") (pintype "bidirectional"))
      (node (ref "S1") (pin "SIG5") (pinfunction "SIG2_SIG5") (pintype "bidirectional"))
      (node (ref "S1") (pin "SIG7") (pinfunction "SIG2_SIG7") (pintype "bidirectional"))
      (node (ref "S1") (pin "SIG9") (pinfunction "SIG2_SIG9") (pintype "bidirectional"))
    )
    (net (code "25") (name "/INT") (class "Default")
      (node (ref "IC1") (pin "30") (pinfunction "PD0(RXD/PCINT16)_30") (pintype "bidirectional"))
      (node (ref "PAD67") (pin "1") (pinfunction "P_1") (pintype "passive"))
      (node (ref "PAD68") (pin "1") (pinfunction "P_1") (pintype "passive"))
      (node (ref "PAD69") (pin "1") (pinfunction "P_1") (pintype "passive"))
      (node (ref "PAD70") (pin "1") (pinfunction "P_1") (pintype "passive"))
      (node (ref "PAD71") (pin "1") (pinfunction "P_1") (pintype "passive"))
      (node (ref "PAD72") (pin "1") (pinfunction "P_1") (pintype "passive"))
      (node (ref "PAD92") (pin "1") (pinfunction "P_1") (pintype "passive"))
    )
    (net (code "26") (name "/N$1") (class "Default")
      (node (ref "PAD86") (pin "1") (pinfunction "P_1") (pintype "passive"))
    )
    (net (code "27") (name "/N$2") (class "Default")
      (node (ref "PAD97") (pin "1") (pinfunction "P_1") (pintype "passive"))
      (node (ref "R3") (pin "2") (pinfunction "2_2") (pintype "passive"))
    )
    (net (code "28") (name "/N$3") (class "Default")
      (node (ref "PAD19") (pin "1") (pinfunction "P_1") (pintype "passive"))
      (node (ref "PAD39") (pin "1") (pinfunction "P_1") (pintype "passive"))
    )
    (net (code "29") (name "/N$4") (class "Default")
      (node (ref "PAD20") (pin "1") (pinfunction "P_1") (pintype "passive"))
      (node (ref "PAD40") (pin "1") (pinfunction "P_1") (pintype "passive"))
    )
    (net (code "30") (name "/N$5") (class "Default")
      (node (ref "PAD21") (pin "1") (pinfunction "P_1") (pintype "passive"))
      (node (ref "PAD41") (pin "1") (pinfunction "P_1") (pintype "passive"))
    )
    (net (code "31") (name "/N$6") (class "Default")
      (node (ref "PAD22") (pin "1") (pinfunction "P_1") (pintype "passive"))
      (node (ref "PAD42") (pin "1") (pinfunction "P_1") (pintype "passive"))
    )
    (net (code "32") (name "/N$8") (class "Default")
      (node (ref "PAD43") (pin "1") (pinfunction "P_1") (pintype "passive"))
    )
    (net (code "33") (name "/N$10") (class "Default")
      (node (ref "PAD99") (pin "1") (pinfunction "P_1") (pintype "passive"))
    )
    (net (code "34") (name "/N$12") (class "Default")
      (node (ref "PAD47") (pin "1") (pinfunction "P_1") (pintype "passive"))
    )
    (net (code "35") (name "/N$17") (class "Default")
      (node (ref "PAD98") (pin "1") (pinfunction "P_1") (pintype "passive"))
      (node (ref "R4") (pin "2") (pinfunction "2_2") (pintype "passive"))
    )
    (net (code "36") (name "/N$20") (class "Default")
      (node (ref "PAD79") (pin "1") (pinfunction "P_1") (pintype "passive"))
    )
    (net (code "37") (name "/RESET") (class "Default")
      (node (ref "IC1") (pin "29") (pinfunction "PC6(/RESET/PCINT14)_29") (pintype "bidirectional"))
      (node (ref "PAD88") (pin "1") (pinfunction "P_1") (pintype "passive"))
    )
    (net (code "38") (name "/SCL") (class "Default")
      (node (ref "IC1") (pin "28") (pinfunction "PC5(ADC5/SCL/PCINT13)_28") (pintype "bidirectional"))
      (node (ref "PAD51") (pin "1") (pinfunction "P_1") (pintype "passive"))
      (node (ref "PAD56") (pin "1") (pinfunction "P_1") (pintype "passive"))
      (node (ref "PAD60") (pin "1") (pinfunction "P_1") (pintype "passive"))
      (node (ref "PAD64") (pin "1") (pinfunction "P_1") (pintype "passive"))
      (node (ref "PAD73") (pin "1") (pinfunction "P_1") (pintype "passive"))
      (node (ref "PAD82") (pin "1") (pinfunction "P_1") (pintype "passive"))
      (node (ref "PAD91") (pin "1") (pinfunction "P_1") (pintype "passive"))
      (node (ref "R1") (pin "1") (pinfunction "1_1") (pintype "passive"))
    )
    (net (code "39") (name "/SDA") (class "Default")
      (node (ref "IC1") (pin "27") (pinfunction "PC4(ADC4/SDA/PCINT12)_27") (pintype "bidirectional"))
      (node (ref "PAD52") (pin "1") (pinfunction "P_1") (pintype "passive"))
      (node (ref "PAD55") (pin "1") (pinfunction "P_1") (pintype "passive"))
      (node (ref "PAD59") (pin "1") (pinfunction "P_1") (pintype "passive"))
      (node (ref "PAD63") (pin "1") (pinfunction "P_1") (pintype "passive"))
      (node (ref "PAD74") (pin "1") (pinfunction "P_1") (pintype "passive"))
      (node (ref "PAD81") (pin "1") (pinfunction "P_1") (pintype "passive"))
      (node (ref "PAD90") (pin "1") (pinfunction "P_1") (pintype "passive"))
      (node (ref "R2") (pin "1") (pinfunction "1_1") (pintype "passive"))
    )
    (net (code "40") (name "/VCC") (class "Default")
      (node (ref "C1") (pin "1") (pinfunction "1_1") (pintype "passive"))
      (node (ref "C2") (pin "1") (pinfunction "1_1") (pintype "passive"))
      (node (ref "IC1") (pin "18") (pinfunction "AVCC_18") (pintype "passive"))
      (node (ref "IC1") (pin "20") (pinfunction "AREF_20") (pintype "passive"))
      (node (ref "IC1") (pin "4") (pinfunction "VCC_4") (pintype "power_in"))
      (node (ref "IC1") (pin "6") (pinfunction "VCC_6") (pintype "power_in"))
      (node (ref "IC2") (pin "2") (pinfunction "VOUT_2") (pintype "output"))
      (node (ref "IC2") (pin "3") (pinfunction "VIN_3") (pintype "input"))
      (node (ref "LED1") (pin "1-VDD") (pinfunction "VDD_1-VDD") (pintype "power_in"))
      (node (ref "LED10") (pin "1-VDD") (pinfunction "VDD_1-VDD") (pintype "power_in"))
      (node (ref "LED11") (pin "1-VDD") (pinfunction "VDD_1-VDD") (pintype "power_in"))
      (node (ref "LED12") (pin "1-VDD") (pinfunction "VDD_1-VDD") (pintype "power_in"))
      (node (ref "LED13") (pin "1-VDD") (pinfunction "VDD_1-VDD") (pintype "power_in"))
      (node (ref "LED14") (pin "1-VDD") (pinfunction "VDD_1-VDD") (pintype "power_in"))
      (node (ref "LED15") (pin "1-VDD") (pinfunction "VDD_1-VDD") (pintype "power_in"))
      (node (ref "LED16") (pin "1-VDD") (pinfunction "VDD_1-VDD") (pintype "power_in"))
      (node (ref "LED2") (pin "1-VDD") (pinfunction "VDD_1-VDD") (pintype "power_in"))
      (node (ref "LED3") (pin "1-VDD") (pinfunction "VDD_1-VDD") (pintype "power_in"))
      (node (ref "LED4") (pin "1-VDD") (pinfunction "VDD_1-VDD") (pintype "power_in"))
      (node (ref "LED5") (pin "1-VDD") (pinfunction "VDD_1-VDD") (pintype "power_in"))
      (node (ref "LED6") (pin "1-VDD") (pinfunction "VDD_1-VDD") (pintype "power_in"))
      (node (ref "LED7") (pin "1-VDD") (pinfunction "VDD_1-VDD") (pintype "power_in"))
      (node (ref "LED8") (pin "1-VDD") (pinfunction "VDD_1-VDD") (pintype "power_in"))
      (node (ref "LED9") (pin "1-VDD") (pinfunction "VDD_1-VDD") (pintype "power_in"))
      (node (ref "PAD104") (pin "1") (pinfunction "P_1") (pintype "passive"))
      (node (ref "PAD46") (pin "1") (pinfunction "P_1") (pintype "passive"))
      (node (ref "PAD48") (pin "1") (pinfunction "P_1") (pintype "passive"))
      (node (ref "PAD49") (pin "1") (pinfunction "P_1") (pintype "passive"))
      (node (ref "PAD54") (pin "1") (pinfunction "P_1") (pintype "passive"))
      (node (ref "PAD57") (pin "1") (pinfunction "P_1") (pintype "passive"))
      (node (ref "PAD62") (pin "1") (pinfunction "P_1") (pintype "passive"))
      (node (ref "PAD66") (pin "1") (pinfunction "P_1") (pintype "passive"))
      (node (ref "PAD76") (pin "1") (pinfunction "P_1") (pintype "passive"))
      (node (ref "PAD83") (pin "1") (pinfunction "P_1") (pintype "passive"))
      (node (ref "PAD94") (pin "1") (pinfunction "P_1") (pintype "passive"))
      (node (ref "PAD96") (pin "1") (pinfunction "P_1") (pintype "passive"))
    )
    (net (code "41") (name "/XTAL1") (class "Default")
      (node (ref "C4") (pin "2") (pinfunction "2_2") (pintype "passive"))
      (node (ref "IC1") (pin "7") (pinfunction "PB6(XTAL1/TOSC1/PCINT6)_7") (pintype "bidirectional"))
      (node (ref "X1") (pin "2") (pinfunction "2_2") (pintype "passive"))
    )
    (net (code "42") (name "/XTAL2") (class "Default")
      (node (ref "C3") (pin "2") (pinfunction "2_2") (pintype "passive"))
      (node (ref "IC1") (pin "8") (pinfunction "PB7(XTAL2/TOSC2/PCINT7)_8") (pintype "bidirectional"))
      (node (ref "X1") (pin "1") (pinfunction "1_1") (pintype "passive"))
    )
    (net (code "43") (name "Net-(LED1-DO)") (class "Default")
      (node (ref "LED1") (pin "2-DOUT") (pinfunction "DO_2-DOUT") (pintype "output"))
      (node (ref "LED2") (pin "4-DIN") (pinfunction "DI_4-DIN") (pintype "input"))
    )
    (net (code "44") (name "Net-(LED2-DO)") (class "Default")
      (node (ref "LED2") (pin "2-DOUT") (pinfunction "DO_2-DOUT") (pintype "output"))
      (node (ref "LED3") (pin "4-DIN") (pinfunction "DI_4-DIN") (pintype "input"))
    )
    (net (code "45") (name "Net-(LED3-DO)") (class "Default")
      (node (ref "LED3") (pin "2-DOUT") (pinfunction "DO_2-DOUT") (pintype "output"))
      (node (ref "LED4") (pin "4-DIN") (pinfunction "DI_4-DIN") (pintype "input"))
    )
    (net (code "46") (name "Net-(LED5-DO)") (class "Default")
      (node (ref "LED5") (pin "2-DOUT") (pinfunction "DO_2-DOUT") (pintype "output"))
      (node (ref "LED6") (pin "4-DIN") (pinfunction "DI_4-DIN") (pintype "input"))
    )
    (net (code "47") (name "Net-(LED6-DO)") (class "Default")
      (node (ref "LED6") (pin "2-DOUT") (pinfunction "DO_2-DOUT") (pintype "output"))
      (node (ref "LED7") (pin "4-DIN") (pinfunction "DI_4-DIN") (pintype "input"))
    )
    (net (code "48") (name "Net-(LED7-DO)") (class "Default")
      (node (ref "LED7") (pin "2-DOUT") (pinfunction "DO_2-DOUT") (pintype "output"))
      (node (ref "LED8") (pin "4-DIN") (pinfunction "DI_4-DIN") (pintype "input"))
    )
    (net (code "49") (name "Net-(LED10-DI)") (class "Default")
      (node (ref "LED10") (pin "4-DIN") (pinfunction "DI_4-DIN") (pintype "input"))
      (node (ref "LED9") (pin "2-DOUT") (pinfunction "DO_2-DOUT") (pintype "output"))
    )
    (net (code "50") (name "Net-(LED10-DO)") (class "Default")
      (node (ref "LED10") (pin "2-DOUT") (pinfunction "DO_2-DOUT") (pintype "output"))
      (node (ref "LED11") (pin "4-DIN") (pinfunction "DI_4-DIN") (pintype "input"))
    )
    (net (code "51") (name "Net-(LED11-DO)") (class "Default")
      (node (ref "LED11") (pin "2-DOUT") (pinfunction "DO_2-DOUT") (pintype "output"))
      (node (ref "LED12") (pin "4-DIN") (pinfunction "DI_4-DIN") (pintype "input"))
    )
    (net (code "52") (name "Net-(LED13-DO)") (class "Default")
      (node (ref "LED13") (pin "2-DOUT") (pinfunction "DO_2-DOUT") (pintype "output"))
      (node (ref "LED14") (pin "4-DIN") (pinfunction "DI_4-DIN") (pintype "input"))
    )
    (net (code "53") (name "Net-(LED14-DO)") (class "Default")
      (node (ref "LED14") (pin "2-DOUT") (pinfunction "DO_2-DOUT") (pintype "output"))
      (node (ref "LED15") (pin "4-DIN") (pinfunction "DI_4-DIN") (pintype "input"))
    )
    (net (code "54") (name "Net-(LED15-DO)") (class "Default")
      (node (ref "LED15") (pin "2-DOUT") (pinfunction "DO_2-DOUT") (pintype "output"))
      (node (ref "LED16") (pin "4-DIN") (pinfunction "DI_4-DIN") (pintype "input"))
    )
    (net (code "55") (name "unconnected-(PAD14-P-Pad1)") (class "Default")
      (node (ref "PAD14") (pin "1") (pinfunction "P_1") (pintype "passive"))
    )
    (net (code "56") (name "unconnected-(PAD77-P-Pad1)") (class "Default")
      (node (ref "PAD77") (pin "1") (pinfunction "P_1") (pintype "passive"))
    )
    (net (code "57") (name "unconnected-(PAD78-P-Pad1)") (class "Default")
      (node (ref "PAD78") (pin "1") (pinfunction "P_1") (pintype "passive"))
    )
    (net (code "58") (name "unconnected-(PAD80-P-Pad1)") (class "Default")
      (node (ref "PAD80") (pin "1") (pinfunction "P_1") (pintype "passive"))
    )
    (net (code "59") (name "unconnected-(PAD84-P-Pad1)") (class "Default")
      (node (ref "PAD84") (pin "1") (pinfunction "P_1") (pintype "passive"))
    )
    (net (code "60") (name "unconnected-(PAD85-P-Pad1)") (class "Default")
      (node (ref "PAD85") (pin "1") (pinfunction "P_1") (pintype "passive"))
    )
  )
)
